# eDP.net
KiCad netlist of a schematic drawn in Altium Designer
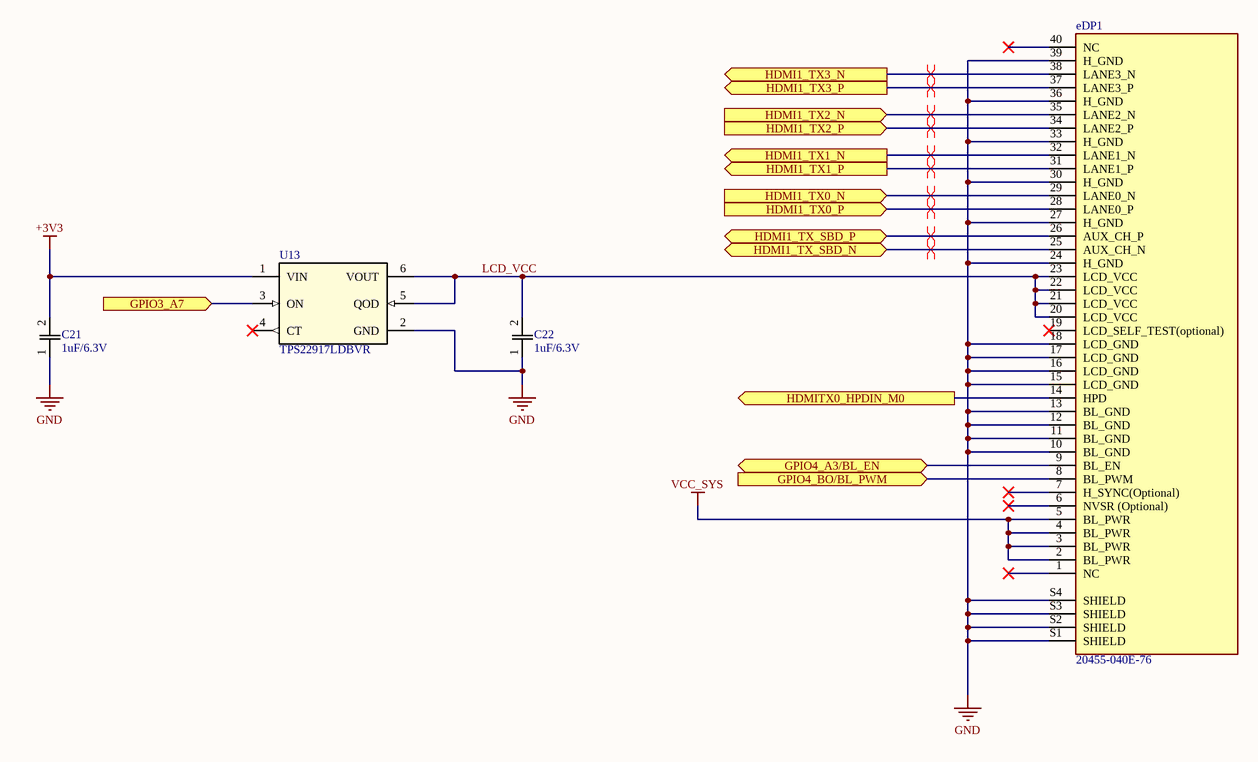
[diagram p0: eDP.SchDoc]

(export (version "E")
  (design (tool "Eeschema 10.0.6"))
  (components
    (comp (ref "C21")
      (value "1uF/6.3V")
      (footprint "C0805")
      (description "1 uF, 6.3 V, ± 10%, X7R, 0805 [2012 Metric] Multilayer Ceramic Capacitor,")
      (fields
        (field (name "MOUSER PART NUMBER") "80-C0805C105K9R")
        (field (name "ARROW PART NUMBER") "C0805C105K9RACTU")
      )
      (libsource (lib "DARKYDEN") (part "C0805C105K9RACTU"))
    )
    (comp (ref "C22")
      (value "1uF/6.3V")
      (footprint "C0805")
      (description "1 uF, 6.3 V, ± 10%, X7R, 0805 [2012 Metric] Multilayer Ceramic Capacitor,")
      (fields
        (field (name "MOUSER PART NUMBER") "80-C0805C105K9R")
        (field (name "ARROW PART NUMBER") "C0805C105K9RACTU")
      )
      (libsource (lib "DARKYDEN") (part "C0805C105K9RACTU"))
    )
    (comp (ref "eDP1")
      (value "20455-040E-76")
      (footprint "IPEX_20455-040E-76:IPEX_20455-040E-76")
      (description "Conn Wire to Board RCP 40 POS 0.5mm Solder RA Side Entry SMDCABLINE® T/R")
      (fields (field (name "MANUFACTURER") "I-PEX"))
      (libsource (lib "DARKYDEN") (part "20455-040E-76"))
    )
    (comp (ref "U13")
      (value "TPS22917LDBVR")
      (footprint "DBV0006_L")
      (fields (field (name "MANUFACTURER") "Texas Instruments"))
      (libsource (lib "TPS22917LDBVR") (part "TPS22917LDBVR"))
    )
  )
  (nets
    (net (code "1") (name "+3V3") (class "Default")
      (node (ref "C21") (pin "2") (pinfunction "2_2") (pintype "passive"))
      (node (ref "U13") (pin "1") (pinfunction "VIN_1") (pintype "power_in"))
    )
    (net (code "2") (name "/GPIO3_A7") (class "Default")
      (node (ref "U13") (pin "3") (pinfunction "ON_3") (pintype "input"))
    )
    (net (code "3") (name "/GPIO4_A3{slash}BL_EN") (class "Default")
      (node (ref "eDP1") (pin "9") (pinfunction "BL_EN_9") (pintype "passive"))
    )
    (net (code "4") (name "/GPIO4_BO{slash}BL_PWM") (class "Default")
      (node (ref "eDP1") (pin "8") (pinfunction "BL_PWM_8") (pintype "passive"))
    )
    (net (code "5") (name "/HDMI1_TX0_N") (class "Default")
      (node (ref "eDP1") (pin "29") (pinfunction "LANE0_N_29") (pintype "passive"))
    )
    (net (code "6") (name "/HDMI1_TX0_P") (class "Default")
      (node (ref "eDP1") (pin "28") (pinfunction "LANE0_P_28") (pintype "passive"))
    )
    (net (code "7") (name "/HDMI1_TX1_N") (class "Default")
      (node (ref "eDP1") (pin "32") (pinfunction "LANE1_N_32") (pintype "passive"))
    )
    (net (code "8") (name "/HDMI1_TX1_P") (class "Default")
      (node (ref "eDP1") (pin "31") (pinfunction "LANE1_P_31") (pintype "passive"))
    )
    (net (code "9") (name "/HDMI1_TX2_N") (class "Default")
      (node (ref "eDP1") (pin "35") (pinfunction "LANE2_N_35") (pintype "passive"))
    )
    (net (code "10") (name "/HDMI1_TX2_P") (class "Default")
      (node (ref "eDP1") (pin "34") (pinfunction "LANE2_P_34") (pintype "passive"))
    )
    (net (code "11") (name "/HDMI1_TX3_N") (class "Default")
      (node (ref "eDP1") (pin "38") (pinfunction "LANE3_N_38") (pintype "passive"))
    )
    (net (code "12") (name "/HDMI1_TX3_P") (class "Default")
      (node (ref "eDP1") (pin "37") (pinfunction "LANE3_P_37") (pintype "passive"))
    )
    (net (code "13") (name "/HDMI1_TX_SBD_N") (class "Default")
      (node (ref "eDP1") (pin "25") (pinfunction "AUX_CH_N_25") (pintype "passive"))
    )
    (net (code "14") (name "/HDMI1_TX_SBD_P") (class "Default")
      (node (ref "eDP1") (pin "26") (pinfunction "AUX_CH_P_26") (pintype "passive"))
    )
    (net (code "15") (name "/HDMITX0_HPDIN_M0") (class "Default")
      (node (ref "eDP1") (pin "14") (pinfunction "HPD_14") (pintype "passive"))
    )
    (net (code "16") (name "/LCD_VCC") (class "Default")
      (node (ref "C22") (pin "2") (pinfunction "2_2") (pintype "passive"))
      (node (ref "U13") (pin "5") (pinfunction "QOD_5") (pintype "input"))
      (node (ref "U13") (pin "6") (pinfunction "VOUT_6") (pintype "power_in"))
      (node (ref "eDP1") (pin "20") (pinfunction "LCD_VCC_20") (pintype "passive"))
      (node (ref "eDP1") (pin "21") (pinfunction "LCD_VCC_21") (pintype "passive"))
      (node (ref "eDP1") (pin "22") (pinfunction "LCD_VCC_22") (pintype "passive"))
      (node (ref "eDP1") (pin "23") (pinfunction "LCD_VCC_23") (pintype "passive"))
    )
    (net (code "17") (name "GND") (class "Default")
      (node (ref "C21") (pin "1") (pinfunction "1_1") (pintype "passive"))
      (node (ref "C22") (pin "1") (pinfunction "1_1") (pintype "passive"))
      (node (ref "U13") (pin "2") (pinfunction "GND_2") (pintype "passive"))
      (node (ref "eDP1") (pin "10") (pinfunction "BL_GND_10") (pintype "passive"))
      (node (ref "eDP1") (pin "11") (pinfunction "BL_GND_11") (pintype "passive"))
      (node (ref "eDP1") (pin "12") (pinfunction "BL_GND_12") (pintype "passive"))
      (node (ref "eDP1") (pin "13") (pinfunction "BL_GND_13") (pintype "passive"))
      (node (ref "eDP1") (pin "15") (pinfunction "LCD_GND_15") (pintype "passive"))
      (node (ref "eDP1") (pin "16") (pinfunction "LCD_GND_16") (pintype "passive"))
      (node (ref "eDP1") (pin "17") (pinfunction "LCD_GND_17") (pintype "passive"))
      (node (ref "eDP1") (pin "18") (pinfunction "LCD_GND_18") (pintype "passive"))
      (node (ref "eDP1") (pin "24") (pinfunction "H_GND_24") (pintype "passive"))
      (node (ref "eDP1") (pin "27") (pinfunction "H_GND_27") (pintype "passive"))
      (node (ref "eDP1") (pin "30") (pinfunction "H_GND_30") (pintype "passive"))
      (node (ref "eDP1") (pin "33") (pinfunction "H_GND_33") (pintype "passive"))
      (node (ref "eDP1") (pin "36") (pinfunction "H_GND_36") (pintype "passive"))
      (node (ref "eDP1") (pin "39") (pinfunction "H_GND_39") (pintype "passive"))
      (node (ref "eDP1") (pin "S1") (pinfunction "SHIELD_S1") (pintype "passive"))
      (node (ref "eDP1") (pin "S2") (pinfunction "SHIELD_S2") (pintype "passive"))
      (node (ref "eDP1") (pin "S3") (pinfunction "SHIELD_S3") (pintype "passive"))
      (node (ref "eDP1") (pin "S4") (pinfunction "SHIELD_S4") (pintype "passive"))
    )
    (net (code "18") (name "VCC_SYS") (class "Default")
      (node (ref "eDP1") (pin "2") (pinfunction "BL_PWR_2") (pintype "passive"))
      (node (ref "eDP1") (pin "3") (pinfunction "BL_PWR_3") (pintype "passive"))
      (node (ref "eDP1") (pin "4") (pinfunction "BL_PWR_4") (pintype "passive"))
      (node (ref "eDP1") (pin "5") (pinfunction "BL_PWR_5") (pintype "passive"))
    )
    (net (code "19") (name "unconnected-(U13-CT-Pad4)") (class "Default")
      (node (ref "U13") (pin "4") (pinfunction "CT_4") (pintype "output+no_connect"))
    )
    (net (code "20") (name "unconnected-(eDP1-H_SYNC(Optional)-Pad7)") (class "Default")
      (node (ref "eDP1") (pin "7") (pinfunction "H_SYNC(Optional)_7") (pintype "passive+no_connect"))
    )
    (net (code "21") (name "unconnected-(eDP1-LCD_SELF_TEST(optional)-Pad19)") (class "Default")
      (node (ref "eDP1") (pin "19") (pinfunction "LCD_SELF_TEST(optional)_19") (pintype "passive+no_connect"))
    )
    (net (code "22") (name "unconnected-(eDP1-NC-Pad1)") (class "Default")
      (node (ref "eDP1") (pin "1") (pinfunction "NC_1") (pintype "passive+no_connect"))
    )
    (net (code "23") (name "unconnected-(eDP1-NC-Pad40)") (class "Default")
      (node (ref "eDP1") (pin "40") (pinfunction "NC_40") (pintype "passive+no_connect"))
    )
    (net (code "24") (name "unconnected-(eDP1-NVSR_(Optional)-Pad6)") (class "Default")
      (node (ref "eDP1") (pin "6") (pinfunction "NVSR_(Optional)_6") (pintype "passive+no_connect"))
    )
  )
)
